# frontend.net
KiCad netlist of a schematic drawn in Altium Designer
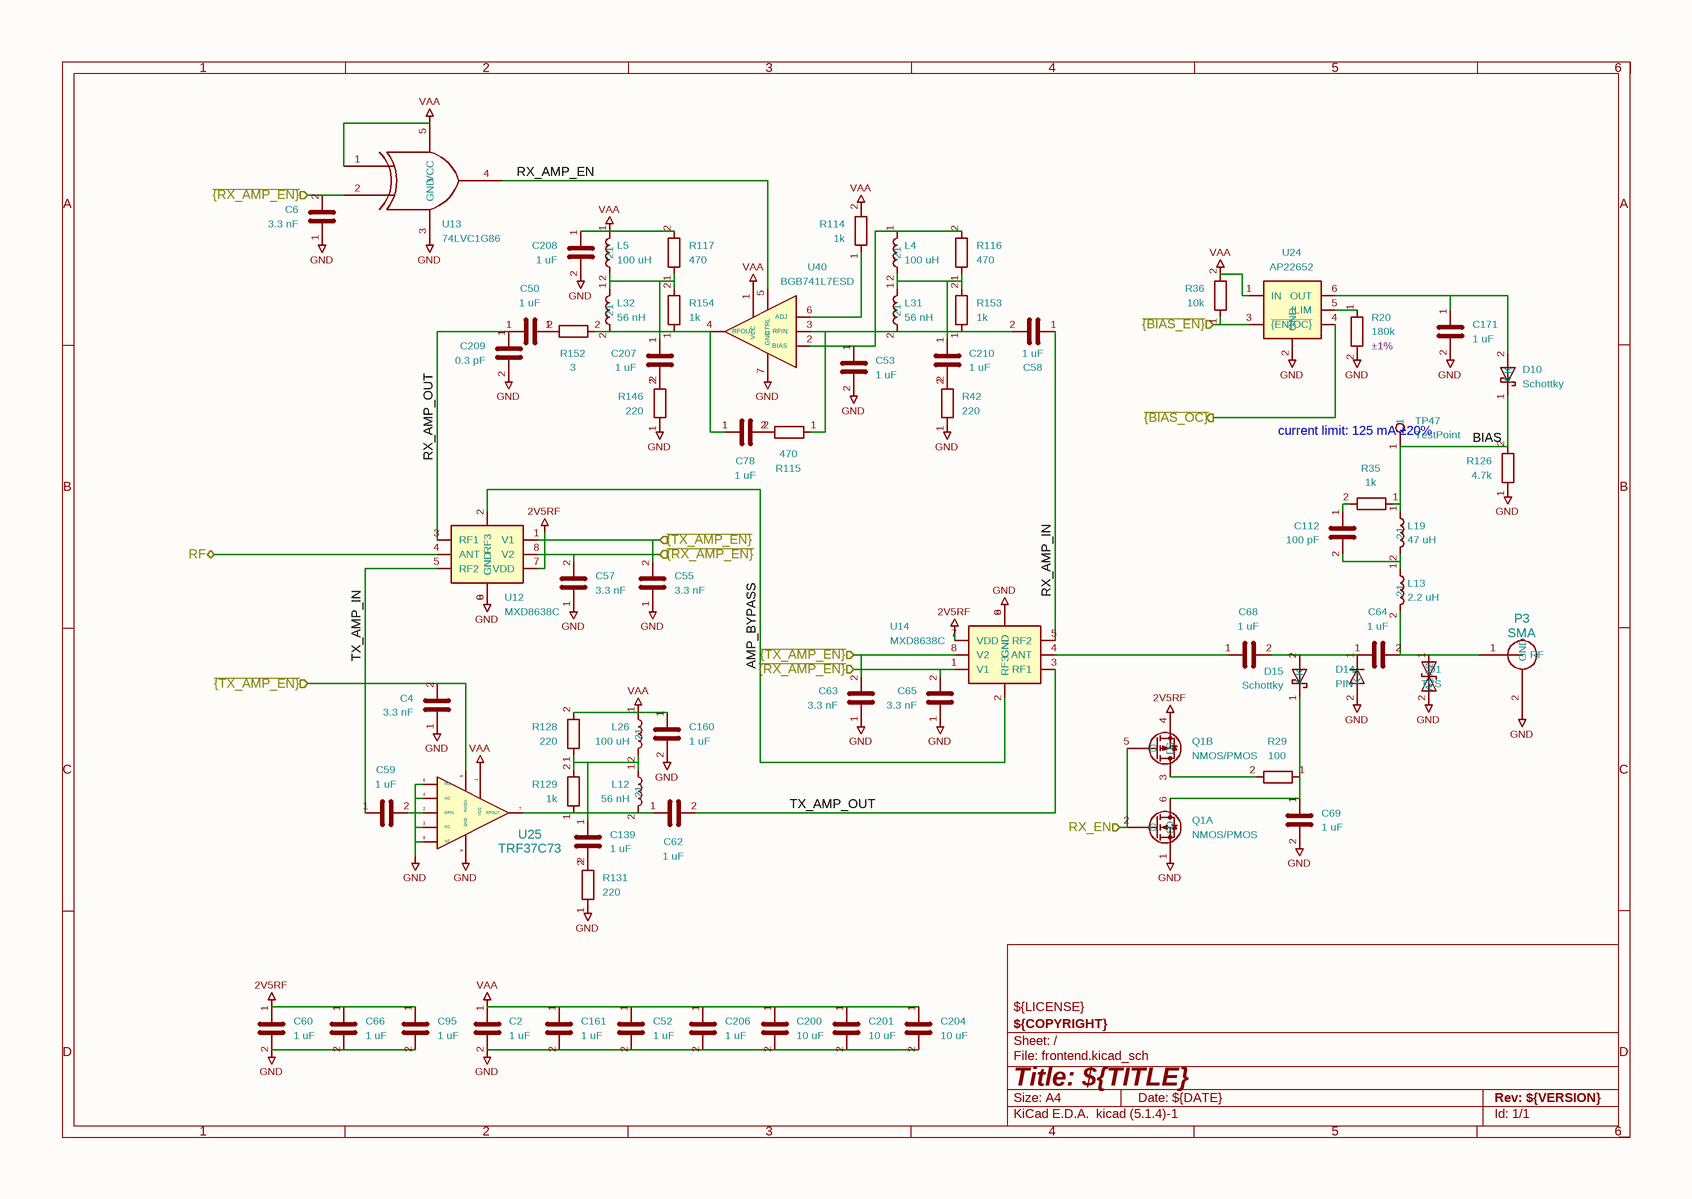
[diagram p0: frontend.SchDoc]

(export (version "E")
  (design (tool "Eeschema 10.0.6"))
  (components
    (comp (ref "C2")
      (value "1 uF")
      (footprint "C_0201_0603Metric")
      (description "CAP CER 1UF 10V X5R 0201")
      (fields (field (name "MANUFACTURER") "Murata") (field (name "PART NUMBER") "GRM033R61A105ME44D"))
      (libsource (lib "Device") (part "C"))
    )
    (comp (ref "C4")
      (value "3.3 nF")
      (footprint "C_0201_0603Metric")
      (description "CAP CER 3300PF 10V X7R 0201")
      (fields (field (name "MANUFACTURER") "Murata") (field (name "PART NUMBER") "GRM033R71A332KA01D"))
      (libsource (lib "Device") (part "C"))
    )
    (comp (ref "C6")
      (value "3.3 nF")
      (footprint "C_0201_0603Metric")
      (description "CAP CER 3300PF 10V X7R 0201")
      (fields (field (name "MANUFACTURER") "Murata") (field (name "PART NUMBER") "GRM033R71A332KA01D"))
      (libsource (lib "Device") (part "C"))
    )
    (comp (ref "C50")
      (value "1 uF")
      (footprint "C_0201_0603Metric")
      (description "CAP CER 1UF 10V X5R 0201")
      (fields (field (name "MANUFACTURER") "Murata") (field (name "PART NUMBER") "GRM033R61A105ME44D"))
      (libsource (lib "Device") (part "C"))
    )
    (comp (ref "C52")
      (value "1 uF")
      (footprint "C_0201_0603Metric")
      (description "CAP CER 1UF 10V X5R 0201")
      (fields (field (name "MANUFACTURER") "Murata") (field (name "PART NUMBER") "GRM033R61A105ME44D"))
      (libsource (lib "Device") (part "C"))
    )
    (comp (ref "C53")
      (value "1 uF")
      (footprint "C_0201_0603Metric")
      (description "CAP CER 1UF 10V X5R 0201")
      (fields (field (name "MANUFACTURER") "Murata") (field (name "PART NUMBER") "GRM033R61A105ME44D"))
      (libsource (lib "Device") (part "C"))
    )
    (comp (ref "C55")
      (value "3.3 nF")
      (footprint "C_0201_0603Metric")
      (description "CAP CER 3300PF 10V X7R 0201")
      (fields (field (name "MANUFACTURER") "Murata") (field (name "PART NUMBER") "GRM033R71A332KA01D"))
      (libsource (lib "Device") (part "C"))
    )
    (comp (ref "C57")
      (value "3.3 nF")
      (footprint "C_0201_0603Metric")
      (description "CAP CER 3300PF 10V X7R 0201")
      (fields (field (name "MANUFACTURER") "Murata") (field (name "PART NUMBER") "GRM033R71A332KA01D"))
      (libsource (lib "Device") (part "C"))
    )
    (comp (ref "C58")
      (value "1 uF")
      (footprint "C_0201_0603Metric")
      (description "CAP CER 1UF 10V X5R 0201")
      (fields (field (name "MANUFACTURER") "Murata") (field (name "PART NUMBER") "GRM033R61A105ME44D"))
      (libsource (lib "Device") (part "C"))
    )
    (comp (ref "C59")
      (value "1 uF")
      (footprint "C_0201_0603Metric")
      (description "CAP CER 1UF 10V X5R 0201")
      (fields (field (name "MANUFACTURER") "Murata") (field (name "PART NUMBER") "GRM033R61A105ME44D"))
      (libsource (lib "Device") (part "C"))
    )
    (comp (ref "C60")
      (value "1 uF")
      (footprint "C_0201_0603Metric")
      (description "CAP CER 1UF 10V X5R 0201")
      (fields (field (name "MANUFACTURER") "Murata") (field (name "PART NUMBER") "GRM033R61A105ME44D"))
      (libsource (lib "Device") (part "C"))
    )
    (comp (ref "C62")
      (value "1 uF")
      (footprint "C_0201_0603Metric")
      (description "CAP CER 1UF 10V X5R 0201")
      (fields (field (name "MANUFACTURER") "Murata") (field (name "PART NUMBER") "GRM033R61A105ME44D"))
      (libsource (lib "Device") (part "C"))
    )
    (comp (ref "C63")
      (value "3.3 nF")
      (footprint "C_0201_0603Metric")
      (description "CAP CER 3300PF 10V X7R 0201")
      (fields (field (name "MANUFACTURER") "Murata") (field (name "PART NUMBER") "GRM033R71A332KA01D"))
      (libsource (lib "Device") (part "C"))
    )
    (comp (ref "C64")
      (value "1 uF")
      (footprint "C_0402_1005Metric")
      (description "CAP CER 1UF 25V X5R 0402")
      (fields (field (name "MANUFACTURER") "Samsung") (field (name "PART NUMBER") "CL05A105KA5NQNC"))
      (libsource (lib "Device") (part "C"))
    )
    (comp (ref "C65")
      (value "3.3 nF")
      (footprint "C_0201_0603Metric")
      (description "CAP CER 3300PF 10V X7R 0201")
      (fields (field (name "MANUFACTURER") "Murata") (field (name "PART NUMBER") "GRM033R71A332KA01D"))
      (libsource (lib "Device") (part "C"))
    )
    (comp (ref "C66")
      (value "1 uF")
      (footprint "C_0201_0603Metric")
      (description "CAP CER 1UF 10V X5R 0201")
      (fields (field (name "MANUFACTURER") "Murata") (field (name "PART NUMBER") "GRM033R61A105ME44D"))
      (libsource (lib "Device") (part "C"))
    )
    (comp (ref "C68")
      (value "1 uF")
      (footprint "C_0201_0603Metric")
      (description "CAP CER 1UF 10V X5R 0201")
      (fields (field (name "MANUFACTURER") "Murata") (field (name "PART NUMBER") "GRM033R61A105ME44D"))
      (libsource (lib "Device") (part "C"))
    )
    (comp (ref "C69")
      (value "1 uF")
      (footprint "C_0201_0603Metric")
      (description "CAP CER 1UF 10V X5R 0201")
      (fields (field (name "MANUFACTURER") "Murata") (field (name "PART NUMBER") "GRM033R61A105ME44D"))
      (libsource (lib "Device") (part "C"))
    )
    (comp (ref "C78")
      (value "1 uF")
      (footprint "C_0201_0603Metric")
      (description "CAP CER 1UF 10V X5R 0201")
      (fields (field (name "MANUFACTURER") "Murata") (field (name "PART NUMBER") "GRM033R61A105ME44D"))
      (libsource (lib "Device") (part "C"))
    )
    (comp (ref "C95")
      (value "1 uF")
      (footprint "C_0201_0603Metric")
      (description "CAP CER 1UF 10V X5R 0201")
      (fields (field (name "MANUFACTURER") "Murata") (field (name "PART NUMBER") "GRM033R61A105ME44D"))
      (libsource (lib "Device") (part "C"))
    )
    (comp (ref "C112")
      (value "100 pF")
      (footprint "C_0201_0603Metric")
      (description "CAP CER 100PF 25V C0G/NP0 0201")
      (fields (field (name "MANUFACTURER") "Murata") (field (name "PART NUMBER") "GRM0335C1E101JA01D"))
      (libsource (lib "Device") (part "C"))
    )
    (comp (ref "C139")
      (value "1 uF")
      (footprint "C_0201_0603Metric")
      (description "CAP CER 1UF 10V X5R 0201")
      (fields (field (name "MANUFACTURER") "Murata") (field (name "PART NUMBER") "GRM033R61A105ME44D"))
      (libsource (lib "Device") (part "C"))
    )
    (comp (ref "C160")
      (value "1 uF")
      (footprint "C_0201_0603Metric")
      (description "CAP CER 1UF 10V X5R 0201")
      (fields (field (name "MANUFACTURER") "Murata") (field (name "PART NUMBER") "GRM033R61A105ME44D"))
      (libsource (lib "Device") (part "C"))
    )
    (comp (ref "C161")
      (value "1 uF")
      (footprint "C_0201_0603Metric")
      (description "CAP CER 1UF 10V X5R 0201")
      (fields (field (name "MANUFACTURER") "Murata") (field (name "PART NUMBER") "GRM033R61A105ME44D"))
      (libsource (lib "Device") (part "C"))
    )
    (comp (ref "C171")
      (value "1 uF")
      (footprint "C_0402_1005Metric")
      (description "CAP CER 1UF 25V X5R 0402")
      (fields (field (name "MANUFACTURER") "Samsung") (field (name "PART NUMBER") "CL05A105KA5NQNC"))
      (libsource (lib "Device") (part "C"))
    )
    (comp (ref "C200")
      (value "10 uF")
      (footprint "C_0805_2012Metric")
      (description "CAP CER 10UF 16V X5R 0805")
      (fields (field (name "MANUFACTURER") "Samsung") (field (name "PART NUMBER") "CL21A106KOQNNNE"))
      (libsource (lib "Device") (part "C"))
    )
    (comp (ref "C201")
      (value "10 uF")
      (footprint "C_0805_2012Metric")
      (description "CAP CER 10UF 16V X5R 0805")
      (fields (field (name "MANUFACTURER") "Samsung") (field (name "PART NUMBER") "CL21A106KOQNNNE"))
      (libsource (lib "Device") (part "C"))
    )
    (comp (ref "C204")
      (value "10 uF")
      (footprint "C_0805_2012Metric")
      (description "CAP CER 10UF 16V X5R 0805")
      (fields (field (name "MANUFACTURER") "Samsung") (field (name "PART NUMBER") "CL21A106KOQNNNE"))
      (libsource (lib "Device") (part "C"))
    )
    (comp (ref "C206")
      (value "1 uF")
      (footprint "C_0201_0603Metric")
      (description "CAP CER 1UF 10V X5R 0201")
      (fields (field (name "MANUFACTURER") "Murata") (field (name "PART NUMBER") "GRM033R61A105ME44D"))
      (libsource (lib "Device") (part "C"))
    )
    (comp (ref "C207")
      (value "1 uF")
      (footprint "C_0201_0603Metric")
      (description "CAP CER 1UF 10V X5R 0201")
      (fields (field (name "MANUFACTURER") "Murata") (field (name "PART NUMBER") "GRM033R61A105ME44D"))
      (libsource (lib "Device") (part "C"))
    )
    (comp (ref "C208")
      (value "1 uF")
      (footprint "C_0201_0603Metric")
      (description "CAP CER 1UF 10V X5R 0201")
      (fields (field (name "MANUFACTURER") "Murata") (field (name "PART NUMBER") "GRM033R61A105ME44D"))
      (libsource (lib "Device") (part "C"))
    )
    (comp (ref "C209")
      (value "0.3 pF")
      (footprint "C_0201_0603Metric")
      (description "CAP CER 0.3PF 25V C0G/NP0 0201")
      (fields (field (name "MANUFACTURER") "Murata") (field (name "PART NUMBER") "GRM0335C1ER30BA01D"))
      (libsource (lib "Device") (part "C"))
    )
    (comp (ref "C210")
      (value "1 uF")
      (footprint "C_0201_0603Metric")
      (description "CAP CER 1UF 10V X5R 0201")
      (fields (field (name "MANUFACTURER") "Murata") (field (name "PART NUMBER") "GRM033R61A105ME44D"))
      (libsource (lib "Device") (part "C"))
    )
    (comp (ref "D1")
      (value "TVS")
      (footprint "TSSLP-2-1")
      (description "Bidirectional transient-voltage-suppression diode")
      (fields (field (name "MANUFACTURER") "Nexperia") (field (name "PART NUMBER") "PESD5V0H1BSFYL"))
      (libsource (lib "Device") (part "D_TVS"))
    )
    (comp (ref "D10")
      (value "Schottky")
      (footprint "TSLP-2-19")
      (description "DIODE SCHOTTKY 40V 1A DSN1006-2")
      (fields (field (name "MANUFACTURER") "Nexperia") (field (name "PART NUMBER") "PMEG4010ESBYL"))
      (libsource (lib "Device") (part "D_Schottky"))
    )
    (comp (ref "D14")
      (value "PIN")
      (footprint "TSLP-2-19")
      (description "RF DIODE PIN 80V 250MW TSLP-2-19")
      (fields (field (name "MANUFACTURER") "Infineon") (field (name "PART NUMBER") "BAR9002ELE6327XTMA1"))
      (libsource (lib "Device") (part "D"))
    )
    (comp (ref "D15")
      (value "Schottky")
      (footprint "TSSLP-2-1")
      (description "DIODE SCHOTTKY 10V 10MA SL2")
      (fields (field (name "MANUFACTURER") "Toshiba") (field (name "PART NUMBER") "JDH2S02SL,L3F"))
      (libsource (lib "Device") (part "D_Schottky"))
    )
    (comp (ref "L4")
      (value "100 uH")
      (footprint "L_TDK_MLZ2012_h1.25mm")
      (description "FIXED IND 100UH 140MA 3.5OHM SMD")
      (fields (field (name "MANUFACTURER") "TDK") (field (name "PART NUMBER") "MLZ2012N101LT000"))
      (libsource (lib "") (part "L_1"))
    )
    (comp (ref "L5")
      (value "100 uH")
      (footprint "L_TDK_MLZ2012_h1.25mm")
      (description "FIXED IND 100UH 140MA 3.5OHM SMD")
      (fields (field (name "MANUFACTURER") "TDK") (field (name "PART NUMBER") "MLZ2012N101LT000"))
      (libsource (lib "") (part "L_1"))
    )
    (comp (ref "L12")
      (value "56 nH")
      (footprint "L_0201_0603Metric")
      (description "FIXED IND 56NH 100MA 3.9 OHM SMD")
      (fields (field (name "MANUFACTURER") "Murata") (field (name "PART NUMBER") "LQP03TN56NJ02D"))
      (libsource (lib "Device") (part "L"))
    )
    (comp (ref "L13")
      (value "2.2 uH")
      (footprint "L_0603_1608Metric")
      (description "FIXED IND 2.2UH 500MA 520MOHM SMD")
      (fields (field (name "MANUFACTURER") "Taiyo Yuden") (field (name "PART NUMBER") "LSQPB160807T2R2M"))
      (libsource (lib "Device") (part "L"))
    )
    (comp (ref "L19")
      (value "47 uH")
      (footprint "L_Taiyo-Yuden_A251818")
      (description "FIXED IND 47UH 120MA 0.84OHM SMD")
      (fields (field (name "MANUFACTURER") "Taiyo Yuden") (field (name "PART NUMBER") "LSQEA251818T470M"))
      (libsource (lib "Device") (part "L"))
    )
    (comp (ref "L26")
      (value "100 uH")
      (footprint "L_TDK_MLZ2012_h1.25mm")
      (description "FIXED IND 100UH 140MA 3.5OHM SMD")
      (fields (field (name "MANUFACTURER") "TDK") (field (name "PART NUMBER") "MLZ2012N101LT000"))
      (libsource (lib "Device") (part "L"))
    )
    (comp (ref "L31")
      (value "56 nH")
      (footprint "L_0201_0603Metric")
      (description "FIXED IND 56NH 100MA 3.9 OHM SMD")
      (fields (field (name "MANUFACTURER") "Murata") (field (name "PART NUMBER") "LQP03TN56NJ02D"))
      (libsource (lib "") (part "L_1"))
    )
    (comp (ref "L32")
      (value "56 nH")
      (footprint "L_0201_0603Metric")
      (description "FIXED IND 56NH 100MA 3.9 OHM SMD")
      (fields (field (name "MANUFACTURER") "Murata") (field (name "PART NUMBER") "LQP03TN56NJ02D"))
      (libsource (lib "") (part "L_1"))
    )
    (comp (ref "P3")
      (value "SMA")
      (footprint "SMA_MyAntenna_A-SMA-KE-16.5A_EdgeMount")
      (description "CONN SMA RCPT STR 50OHM EDGE MNT")
      (fields (field (name "MANUFACTURER") "MyAntenna") (field (name "PART NUMBER") "A-SMA-KE-16.5A"))
      (libsource (lib "hackrf") (part "GSG-RF-CONN"))
    )
    (comp (ref "Q1")
      (value "NMOS/PMOS")
      (footprint "SOT-563")
      (description "Dual NMOS/PMOS transistor, 6 pin package")
      (fields (field (name "MANUFACTURER") "Diodes Inc.") (field (name "PART NUMBER") "DMC2400UV-7"))
      (libsource (lib "praline") (part "Q_Dual_NMOS_PMOS_S1G1D2S2G2D1"))
    )
    (comp (ref "R20")
      (value "180k")
      (footprint "R_0402_1005Metric")
      (description "RES 180K OHM 1% 1/16W 0402")
      (fields
        (field (name "MANUFACTURER") "Yageo")
        (field (name "PART NUMBER") "RC0402FR-07180KL")
        (field (name "TOLERANCE") "±1%")
      )
      (libsource (lib "Device") (part "R"))
    )
    (comp (ref "R29")
      (value "100")
      (footprint "R_0201_0603Metric")
      (description "RES 100 OHM 5% 1/20W 0201")
      (fields (field (name "MANUFACTURER") "Yageo") (field (name "PART NUMBER") "RC0201JR-07100RL"))
      (libsource (lib "") (part "R_3"))
    )
    (comp (ref "R35")
      (value "1k")
      (footprint "R_0201_0603Metric")
      (description "RES 1K OHM 1% 1/20W 0201")
      (fields (field (name "MANUFACTURER") "Yageo") (field (name "PART NUMBER") "RC0201FR-071KL"))
      (libsource (lib "Device") (part "R"))
    )
    (comp (ref "R36")
      (value "10k")
      (footprint "R_0402_1005Metric")
      (description "RES 10K OHM 1/16W 5% 0402 SMD")
      (fields (field (name "MANUFACTURER") "Yageo") (field (name "PART NUMBER") "RC0402JR-0710KL"))
      (libsource (lib "") (part "R_1"))
    )
    (comp (ref "R42")
      (value "220")
      (footprint "R_0201_0603Metric")
      (description "RES 220 OHM 5% 1/20W 0201")
      (fields (field (name "MANUFACTURER") "Yageo") (field (name "PART NUMBER") "RC0201JR-07220RL"))
      (libsource (lib "") (part "R_1"))
    )
    (comp (ref "R114")
      (value "1k")
      (footprint "R_0201_0603Metric")
      (description "RES 1K OHM 1% 1/20W 0201")
      (fields (field (name "MANUFACTURER") "Yageo") (field (name "PART NUMBER") "RC0201FR-071KL"))
      (libsource (lib "") (part "R_2"))
    )
    (comp (ref "R115")
      (value "470")
      (footprint "R_0201_0603Metric")
      (description "RES 470 OHM 5% 1/20W 0201")
      (fields (field (name "MANUFACTURER") "Yageo") (field (name "PART NUMBER") "RC0201JR-07470RL"))
      (libsource (lib "") (part "R_3"))
    )
    (comp (ref "R116")
      (value "470")
      (footprint "R_0201_0603Metric")
      (description "RES 470 OHM 5% 1/20W 0201")
      (fields (field (name "MANUFACTURER") "Yageo") (field (name "PART NUMBER") "RC0201JR-07470RL"))
      (libsource (lib "") (part "R_1"))
    )
    (comp (ref "R117")
      (value "470")
      (footprint "R_0201_0603Metric")
      (description "RES 470 OHM 5% 1/20W 0201")
      (fields (field (name "MANUFACTURER") "Yageo") (field (name "PART NUMBER") "RC0201JR-07470RL"))
      (libsource (lib "") (part "R_1"))
    )
    (comp (ref "R126")
      (value "4.7k")
      (footprint "R_0201_0603Metric")
      (description "RES 4.7K OHM 1% 1/20W 0201")
      (fields (field (name "MANUFACTURER") "Yageo") (field (name "PART NUMBER") "RC0201FR-074K7L"))
      (libsource (lib "") (part "R_1"))
    )
    (comp (ref "R128")
      (value "220")
      (footprint "R_0201_0603Metric")
      (description "RES 220 OHM 5% 1/20W 0201")
      (fields (field (name "MANUFACTURER") "Yageo") (field (name "PART NUMBER") "RC0201JR-07220RL"))
      (libsource (lib "") (part "R_2"))
    )
    (comp (ref "R129")
      (value "1k")
      (footprint "R_0201_0603Metric")
      (description "RES 1K OHM 1% 1/20W 0201")
      (fields (field (name "MANUFACTURER") "Yageo") (field (name "PART NUMBER") "RC0201FR-071KL"))
      (libsource (lib "") (part "R_2"))
    )
    (comp (ref "R131")
      (value "220")
      (footprint "R_0201_0603Metric")
      (description "RES 220 OHM 5% 1/20W 0201")
      (fields (field (name "MANUFACTURER") "Yageo") (field (name "PART NUMBER") "RC0201JR-07220RL"))
      (libsource (lib "") (part "R_1"))
    )
    (comp (ref "R146")
      (value "220")
      (footprint "R_0201_0603Metric")
      (description "RES 220 OHM 5% 1/20W 0201")
      (fields (field (name "MANUFACTURER") "Yageo") (field (name "PART NUMBER") "RC0201JR-07220RL"))
      (libsource (lib "") (part "R_2"))
    )
    (comp (ref "R152")
      (value "3")
      (footprint "R_0201_0603Metric")
      (description "RES 3 OHM 5% 1/20W 0201")
      (fields (field (name "MANUFACTURER") "Yageo") (field (name "PART NUMBER") "RC0201JR-073RL"))
      (libsource (lib "") (part "R_1"))
    )
    (comp (ref "R153")
      (value "1k")
      (footprint "R_0201_0603Metric")
      (description "RES 1K OHM 1% 1/20W 0201")
      (fields (field (name "MANUFACTURER") "Yageo") (field (name "PART NUMBER") "RC0201FR-071KL"))
      (libsource (lib "") (part "R_1"))
    )
    (comp (ref "R154")
      (value "1k")
      (footprint "R_0201_0603Metric")
      (description "RES 1K OHM 1% 1/20W 0201")
      (fields (field (name "MANUFACTURER") "Yageo") (field (name "PART NUMBER") "RC0201FR-071KL"))
      (libsource (lib "") (part "R_1"))
    )
    (comp (ref "TP47")
      (value "TestPoint")
      (footprint "TestPoint_Pad_D1.0mm")
      (libsource (lib "Connector") (part "TestPoint"))
    )
    (comp (ref "U12")
      (value "MXD8638C")
      (footprint "MXD8638C")
      (description "Wideband RF SP3T Switch")
      (fields (field (name "MANUFACTURER") "Maxscend"))
      (libsource (lib "praline") (part "MXD8638"))
    )
    (comp (ref "U13")
      (value "74LVC1G86")
      (footprint "SOT-353_SC-70-5")
      (description "IC GATE XOR 1CH 2-INP SC70-5")
      (fields (field (name "MANUFACTURER") "UMW") (field (name "PART NUMBER") "SN74LVC1G86DCKR"))
      (libsource (lib "74xGxx") (part "74LVC1G86"))
    )
    (comp (ref "U14")
      (value "MXD8638C")
      (footprint "MXD8638C")
      (description "Wideband RF SP3T Switch")
      (fields (field (name "MANUFACTURER") "Maxscend"))
      (libsource (lib "") (part "MXD8638_1"))
    )
    (comp (ref "U24")
      (value "AP22652")
      (footprint "TSOP-6_1.65x3.05mm_P0.95mm")
      (description "LOAD SWITCH,SOT26,T&R,3K")
      (fields (field (name "MANUFACTURER") "Diodes Inc.") (field (name "PART NUMBER") "AP22652W6-7"))
      (libsource (lib "Power_Management") (part "BD2243G"))
    )
    (comp (ref "U25")
      (value "TRF37C73")
      (footprint "WSON-8-1EP_2x2mm_P0.5mm_EP0.9x1.6mm")
      (description "IC RF AMP 1MHZ-6GHZ 8WSON")
      (fields (field (name "MANUFACTURER") "Texas Instruments") (field (name "PART NUMBER") "TRF37C73IDSGR"))
      (libsource (lib "praline") (part "TRF37A73"))
    )
    (comp (ref "U40")
      (value "BGB741L7ESD")
      (footprint "TSLP-7-1")
      (description "IC AMP CELL 50MHZ-3.5GHZ TSLP7-1")
      (fields (field (name "MANUFACTURER") "Infineon") (field (name "PART NUMBER") "BGB741L7ESDE6327XTSA1"))
      (libsource (lib "praline") (part "BGB741L7ESD"))
    )
  )
  (nets
    (net (code "1") (name "/AMP_BYPASS") (class "Default")
      (node (ref "U12") (pin "2") (pinfunction "RF3_2") (pintype "passive"))
      (node (ref "U14") (pin "2") (pinfunction "RF3_2") (pintype "passive"))
    )
    (net (code "2") (name "/BIAS") (class "Default")
      (node (ref "D10") (pin "1") (pinfunction "K_1") (pintype "passive"))
      (node (ref "L19") (pin "1") (pinfunction "1_1") (pintype "passive"))
      (node (ref "R126") (pin "2") (pinfunction "2_2") (pintype "passive"))
      (node (ref "R35") (pin "1") (pinfunction "1_1") (pintype "passive"))
      (node (ref "TP47") (pin "1") (pinfunction "1_1") (pintype "passive"))
    )
    (net (code "3") (name "/RF") (class "Default")
      (node (ref "U12") (pin "4") (pinfunction "ANT_4") (pintype "passive"))
    )
    (net (code "4") (name "/RX_AMP_EN") (class "Default")
      (node (ref "U13") (pin "4") (pinfunction "4_4") (pintype "passive"))
      (node (ref "U40") (pin "5") (pinfunction "CTRL_5") (pintype "passive"))
    )
    (net (code "5") (name "/RX_AMP_IN") (class "Default")
      (node (ref "C58") (pin "1") (pinfunction "1_1") (pintype "passive"))
      (node (ref "U14") (pin "5") (pinfunction "RF2_5") (pintype "passive"))
    )
    (net (code "6") (name "/RX_AMP_OUT") (class "Default")
      (node (ref "C209") (pin "1") (pinfunction "1_1") (pintype "passive"))
      (node (ref "C50") (pin "1") (pinfunction "1_1") (pintype "passive"))
      (node (ref "U12") (pin "3") (pinfunction "RF1_3") (pintype "passive"))
    )
    (net (code "7") (name "/RX_EN") (class "Default")
      (node (ref "Q1") (pin "2") (pinfunction "G_2") (pintype "passive"))
      (node (ref "Q1") (pin "5") (pinfunction "G_5") (pintype "passive"))
    )
    (net (code "8") (name "/TX_AMP_IN") (class "Default")
      (node (ref "C59") (pin "1") (pinfunction "1_1") (pintype "passive"))
      (node (ref "U12") (pin "5") (pinfunction "RF2_5") (pintype "passive"))
    )
    (net (code "9") (name "/TX_AMP_OUT") (class "Default")
      (node (ref "C62") (pin "2") (pinfunction "2_2") (pintype "passive"))
      (node (ref "U14") (pin "3") (pinfunction "RF1_3") (pintype "passive"))
    )
    (net (code "10") (name "/~{{BIAS_EN}}") (class "Default")
      (node (ref "R36") (pin "1") (pinfunction "1_1") (pintype "passive"))
      (node (ref "U24") (pin "3") (pinfunction "~{{EN}}_3") (pintype "passive"))
    )
    (net (code "11") (name "/~{{BIAS_OC}}") (class "Default")
      (node (ref "U24") (pin "4") (pinfunction "~{{OC}}_4") (pintype "passive"))
    )
    (net (code "12") (name "/~{{RX_AMP_EN}}") (class "Default")
      (node (ref "C57") (pin "2") (pinfunction "2_2") (pintype "passive"))
      (node (ref "C6") (pin "2") (pinfunction "2_2") (pintype "passive"))
      (node (ref "C65") (pin "2") (pinfunction "2_2") (pintype "passive"))
      (node (ref "U12") (pin "8") (pinfunction "V2_8") (pintype "passive"))
      (node (ref "U13") (pin "2") (pinfunction "2_2") (pintype "passive"))
      (node (ref "U14") (pin "1") (pinfunction "V1_1") (pintype "passive"))
    )
    (net (code "13") (name "/~{{TX_AMP_EN}}") (class "Default")
      (node (ref "C4") (pin "2") (pinfunction "2_2") (pintype "passive"))
      (node (ref "C55") (pin "2") (pinfunction "2_2") (pintype "passive"))
      (node (ref "C63") (pin "2") (pinfunction "2_2") (pintype "passive"))
      (node (ref "U12") (pin "1") (pinfunction "V1_1") (pintype "passive"))
      (node (ref "U14") (pin "8") (pinfunction "V2_8") (pintype "passive"))
      (node (ref "U25") (pin "5") (pinfunction "PWDN_5") (pintype "passive"))
    )
    (net (code "14") (name "2V5RF") (class "Default")
      (node (ref "C60") (pin "1") (pinfunction "1_1") (pintype "passive"))
      (node (ref "C66") (pin "1") (pinfunction "1_1") (pintype "passive"))
      (node (ref "C95") (pin "1") (pinfunction "1_1") (pintype "passive"))
      (node (ref "Q1") (pin "4") (pinfunction "S_4") (pintype "passive"))
      (node (ref "U12") (pin "7") (pinfunction "VDD_7") (pintype "passive"))
      (node (ref "U14") (pin "7") (pinfunction "VDD_7") (pintype "passive"))
    )
    (net (code "15") (name "GND") (class "Default")
      (node (ref "C160") (pin "2") (pinfunction "2_2") (pintype "passive"))
      (node (ref "C161") (pin "2") (pinfunction "2_2") (pintype "passive"))
      (node (ref "C171") (pin "2") (pinfunction "2_2") (pintype "passive"))
      (node (ref "C2") (pin "2") (pinfunction "2_2") (pintype "passive"))
      (node (ref "C200") (pin "2") (pinfunction "2_2") (pintype "passive"))
      (node (ref "C201") (pin "2") (pinfunction "2_2") (pintype "passive"))
      (node (ref "C204") (pin "2") (pinfunction "2_2") (pintype "passive"))
      (node (ref "C206") (pin "2") (pinfunction "2_2") (pintype "passive"))
      (node (ref "C208") (pin "2") (pinfunction "2_2") (pintype "passive"))
      (node (ref "C209") (pin "2") (pinfunction "2_2") (pintype "passive"))
      (node (ref "C4") (pin "1") (pinfunction "1_1") (pintype "passive"))
      (node (ref "C52") (pin "2") (pinfunction "2_2") (pintype "passive"))
      (node (ref "C53") (pin "2") (pinfunction "2_2") (pintype "passive"))
      (node (ref "C55") (pin "1") (pinfunction "1_1") (pintype "passive"))
      (node (ref "C57") (pin "1") (pinfunction "1_1") (pintype "passive"))
      (node (ref "C6") (pin "1") (pinfunction "1_1") (pintype "passive"))
      (node (ref "C60") (pin "2") (pinfunction "2_2") (pintype "passive"))
      (node (ref "C63") (pin "1") (pinfunction "1_1") (pintype "passive"))
      (node (ref "C65") (pin "1") (pinfunction "1_1") (pintype "passive"))
      (node (ref "C66") (pin "2") (pinfunction "2_2") (pintype "passive"))
      (node (ref "C69") (pin "2") (pinfunction "2_2") (pintype "passive"))
      (node (ref "C95") (pin "2") (pinfunction "2_2") (pintype "passive"))
      (node (ref "D1") (pin "2") (pinfunction "A2_2") (pintype "passive"))
      (node (ref "D14") (pin "2") (pinfunction "A_2") (pintype "passive"))
      (node (ref "P3") (pin "2") (pinfunction "GND_2") (pintype "passive"))
      (node (ref "Q1") (pin "1") (pinfunction "S_1") (pintype "passive"))
      (node (ref "R126") (pin "1") (pinfunction "1_1") (pintype "passive"))
      (node (ref "R131") (pin "1") (pinfunction "1_1") (pintype "passive"))
      (node (ref "R146") (pin "1") (pinfunction "1_1") (pintype "passive"))
      (node (ref "R20") (pin "2") (pinfunction "2_2") (pintype "passive"))
      (node (ref "R42") (pin "1") (pinfunction "1_1") (pintype "passive"))
      (node (ref "U12") (pin "6") (pinfunction "GND_6") (pintype "passive"))
      (node (ref "U12") (pin "9") (pinfunction "GND_9") (pintype "passive"))
      (node (ref "U13") (pin "3") (pinfunction "GND_3") (pintype "passive"))
      (node (ref "U14") (pin "6") (pinfunction "GND_6") (pintype "passive"))
      (node (ref "U14") (pin "9") (pinfunction "GND_9") (pintype "passive"))
      (node (ref "U24") (pin "2") (pinfunction "GND_2") (pintype "passive"))
      (node (ref "U25") (pin "3") (pinfunction "NC_3") (pintype "passive"))
      (node (ref "U25") (pin "4") (pinfunction "NC_4") (pintype "passive"))
      (node (ref "U25") (pin "6") (pinfunction "NC_6") (pintype "passive"))
      (node (ref "U25") (pin "8") (pinfunction "NC_8") (pintype "passive"))
      (node (ref "U25") (pin "9") (pinfunction "GND_9") (pintype "passive"))
      (node (ref "U40") (pin "7") (pinfunction "GND_7") (pintype "passive"))
    )
    (net (code "16") (name "Net-(C50-Pad2)") (class "Default")
      (node (ref "C50") (pin "2") (pinfunction "2_2") (pintype "passive"))
      (node (ref "R152") (pin "1") (pinfunction "1_1") (pintype "passive"))
    )
    (net (code "17") (name "Net-(C78-Pad2)") (class "Default")
      (node (ref "C78") (pin "2") (pinfunction "2_2") (pintype "passive"))
      (node (ref "R115") (pin "2") (pinfunction "2_2") (pintype "passive"))
    )
    (net (code "18") (name "Net-(C112-Pad1)") (class "Default")
      (node (ref "C112") (pin "1") (pinfunction "1_1") (pintype "passive"))
      (node (ref "R35") (pin "2") (pinfunction "2_2") (pintype "passive"))
    )
    (net (code "19") (name "Net-(C112-Pad2)") (class "Default")
      (node (ref "C112") (pin "2") (pinfunction "2_2") (pintype "passive"))
      (node (ref "L13") (pin "1") (pinfunction "1_1") (pintype "passive"))
      (node (ref "L19") (pin "2") (pinfunction "2_2") (pintype "passive"))
    )
    (net (code "20") (name "Net-(C139-Pad1)") (class "Default")
      (node (ref "C139") (pin "1") (pinfunction "1_1") (pintype "passive"))
      (node (ref "L12") (pin "1") (pinfunction "1_1") (pintype "passive"))
      (node (ref "L26") (pin "2") (pinfunction "2_2") (pintype "passive"))
      (node (ref "R128") (pin "1") (pinfunction "1_1") (pintype "passive"))
      (node (ref "R129") (pin "2") (pinfunction "2_2") (pintype "passive"))
    )
    (net (code "21") (name "Net-(C139-Pad2)") (class "Default")
      (node (ref "C139") (pin "2") (pinfunction "2_2") (pintype "passive"))
      (node (ref "R131") (pin "2") (pinfunction "2_2") (pintype "passive"))
    )
    (net (code "22") (name "Net-(C207-Pad1)") (class "Default")
      (node (ref "C207") (pin "1") (pinfunction "1_1") (pintype "passive"))
      (node (ref "L32") (pin "1") (pinfunction "1_1") (pintype "passive"))
      (node (ref "L5") (pin "2") (pinfunction "2_2") (pintype "passive"))
      (node (ref "R117") (pin "1") (pinfunction "1_1") (pintype "passive"))
      (node (ref "R154") (pin "2") (pinfunction "2_2") (pintype "passive"))
    )
    (net (code "23") (name "Net-(C207-Pad2)") (class "Default")
      (node (ref "C207") (pin "2") (pinfunction "2_2") (pintype "passive"))
      (node (ref "R146") (pin "2") (pinfunction "2_2") (pintype "passive"))
    )
    (net (code "24") (name "Net-(C210-Pad1)") (class "Default")
      (node (ref "C210") (pin "1") (pinfunction "1_1") (pintype "passive"))
      (node (ref "L31") (pin "1") (pinfunction "1_1") (pintype "passive"))
      (node (ref "L4") (pin "2") (pinfunction "2_2") (pintype "passive"))
      (node (ref "R116") (pin "1") (pinfunction "1_1") (pintype "passive"))
      (node (ref "R153") (pin "2") (pinfunction "2_2") (pintype "passive"))
    )
    (net (code "25") (name "Net-(C210-Pad2)") (class "Default")
      (node (ref "C210") (pin "2") (pinfunction "2_2") (pintype "passive"))
      (node (ref "R42") (pin "2") (pinfunction "2_2") (pintype "passive"))
    )
    (net (code "26") (name "Net-(D1-A1)") (class "Default")
      (node (ref "C64") (pin "2") (pinfunction "2_2") (pintype "passive"))
      (node (ref "D1") (pin "1") (pinfunction "A1_1") (pintype "passive"))
      (node (ref "L13") (pin "2") (pinfunction "2_2") (pintype "passive"))
      (node (ref "P3") (pin "1") (pinfunction "RF_1") (pintype "passive"))
    )
    (net (code "27") (name "Net-(D10-A)") (class "Default")
      (node (ref "C171") (pin "1") (pinfunction "1_1") (pintype "passive"))
      (node (ref "D10") (pin "2") (pinfunction "A_2") (pintype "passive"))
      (node (ref "U24") (pin "6") (pinfunction "OUT_6") (pintype "passive"))
    )
    (net (code "28") (name "Net-(D14-K)") (class "Default")
      (node (ref "C64") (pin "1") (pinfunction "1_1") (pintype "passive"))
      (node (ref "C68") (pin "2") (pinfunction "2_2") (pintype "passive"))
      (node (ref "D14") (pin "1") (pinfunction "K_1") (pintype "passive"))
      (node (ref "D15") (pin "2") (pinfunction "A_2") (pintype "passive"))
    )
    (net (code "29") (name "Net-(D15-K)") (class "Default")
      (node (ref "C69") (pin "1") (pinfunction "1_1") (pintype "passive"))
      (node (ref "D15") (pin "1") (pinfunction "K_1") (pintype "passive"))
      (node (ref "Q1") (pin "6") (pinfunction "D_6") (pintype "passive"))
      (node (ref "R29") (pin "1") (pinfunction "1_1") (pintype "passive"))
    )
    (net (code "30") (name "Net-(Q1B-D)") (class "Default")
      (node (ref "Q1") (pin "3") (pinfunction "D_3") (pintype "passive"))
      (node (ref "R29") (pin "2") (pinfunction "2_2") (pintype "passive"))
    )
    (net (code "31") (name "Net-(U14-ANT)") (class "Default")
      (node (ref "C68") (pin "1") (pinfunction "1_1") (pintype "passive"))
      (node (ref "U14") (pin "4") (pinfunction "ANT_4") (pintype "passive"))
    )
    (net (code "32") (name "Net-(U24-ILIM)") (class "Default")
      (node (ref "R20") (pin "1") (pinfunction "1_1") (pintype "passive"))
      (node (ref "U24") (pin "5") (pinfunction "ILIM_5") (pintype "passive"))
    )
    (net (code "33") (name "Net-(U25-RFIN)") (class "Default")
      (node (ref "C59") (pin "2") (pinfunction "2_2") (pintype "passive"))
      (node (ref "U25") (pin "2") (pinfunction "RFIN_2") (pintype "passive"))
    )
    (net (code "34") (name "Net-(U25-RFOUT)") (class "Default")
      (node (ref "C62") (pin "1") (pinfunction "1_1") (pintype "passive"))
      (node (ref "L12") (pin "2") (pinfunction "2_2") (pintype "passive"))
      (node (ref "R129") (pin "1") (pinfunction "1_1") (pintype "passive"))
      (node (ref "U25") (pin "7") (pinfunction "RFOUT_7") (pintype "passive"))
    )
    (net (code "35") (name "Net-(U40-ADJ)") (class "Default")
      (node (ref "R114") (pin "1") (pinfunction "1_1") (pintype "passive"))
      (node (ref "U40") (pin "6") (pinfunction "ADJ_6") (pintype "passive"))
    )
    (net (code "36") (name "Net-(U40-BIAS)") (class "Default")
      (node (ref "C53") (pin "1") (pinfunction "1_1") (pintype "passive"))
      (node (ref "L4") (pin "1") (pinfunction "1_1") (pintype "passive"))
      (node (ref "R116") (pin "2") (pinfunction "2_2") (pintype "passive"))
      (node (ref "U40") (pin "2") (pinfunction "BIAS_2") (pintype "passive"))
    )
    (net (code "37") (name "Net-(U40-RFIN)") (class "Default")
      (node (ref "C58") (pin "2") (pinfunction "2_2") (pintype "passive"))
      (node (ref "L31") (pin "2") (pinfunction "2_2") (pintype "passive"))
      (node (ref "R115") (pin "1") (pinfunction "1_1") (pintype "passive"))
      (node (ref "R153") (pin "1") (pinfunction "1_1") (pintype "passive"))
      (node (ref "U40") (pin "3") (pinfunction "RFIN_3") (pintype "passive"))
    )
    (net (code "38") (name "Net-(U40-RFOUT)") (class "Default")
      (node (ref "C78") (pin "1") (pinfunction "1_1") (pintype "passive"))
      (node (ref "L32") (pin "2") (pinfunction "2_2") (pintype "passive"))
      (node (ref "R152") (pin "2") (pinfunction "2_2") (pintype "passive"))
      (node (ref "R154") (pin "1") (pinfunction "1_1") (pintype "passive"))
      (node (ref "U40") (pin "4") (pinfunction "RFOUT_4") (pintype "passive"))
    )
    (net (code "39") (name "VAA") (class "Default")
      (node (ref "C160") (pin "1") (pinfunction "1_1") (pintype "passive"))
      (node (ref "C161") (pin "1") (pinfunction "1_1") (pintype "passive"))
      (node (ref "C2") (pin "1") (pinfunction "1_1") (pintype "passive"))
      (node (ref "C200") (pin "1") (pinfunction "1_1") (pintype "passive"))
      (node (ref "C201") (pin "1") (pinfunction "1_1") (pintype "passive"))
      (node (ref "C204") (pin "1") (pinfunction "1_1") (pintype "passive"))
      (node (ref "C206") (pin "1") (pinfunction "1_1") (pintype "passive"))
      (node (ref "C208") (pin "1") (pinfunction "1_1") (pintype "passive"))
      (node (ref "C52") (pin "1") (pinfunction "1_1") (pintype "passive"))
      (node (ref "L26") (pin "1") (pinfunction "1_1") (pintype "passive"))
      (node (ref "L5") (pin "1") (pinfunction "1_1") (pintype "passive"))
      (node (ref "R114") (pin "2") (pinfunction "2_2") (pintype "passive"))
      (node (ref "R117") (pin "2") (pinfunction "2_2") (pintype "passive"))
      (node (ref "R128") (pin "2") (pinfunction "2_2") (pintype "passive"))
      (node (ref "R36") (pin "2") (pinfunction "2_2") (pintype "passive"))
      (node (ref "U13") (pin "1") (pinfunction "1_1") (pintype "passive"))
      (node (ref "U13") (pin "5") (pinfunction "VCC_5") (pintype "passive"))
      (node (ref "U24") (pin "1") (pinfunction "IN_1") (pintype "passive"))
      (node (ref "U25") (pin "1") (pinfunction "VCC_1") (pintype "passive"))
      (node (ref "U40") (pin "1") (pinfunction "VCC_1") (pintype "passive"))
    )
  )
)
